# MODULOS.net
KiCad netlist of a schematic drawn in Altium Designer
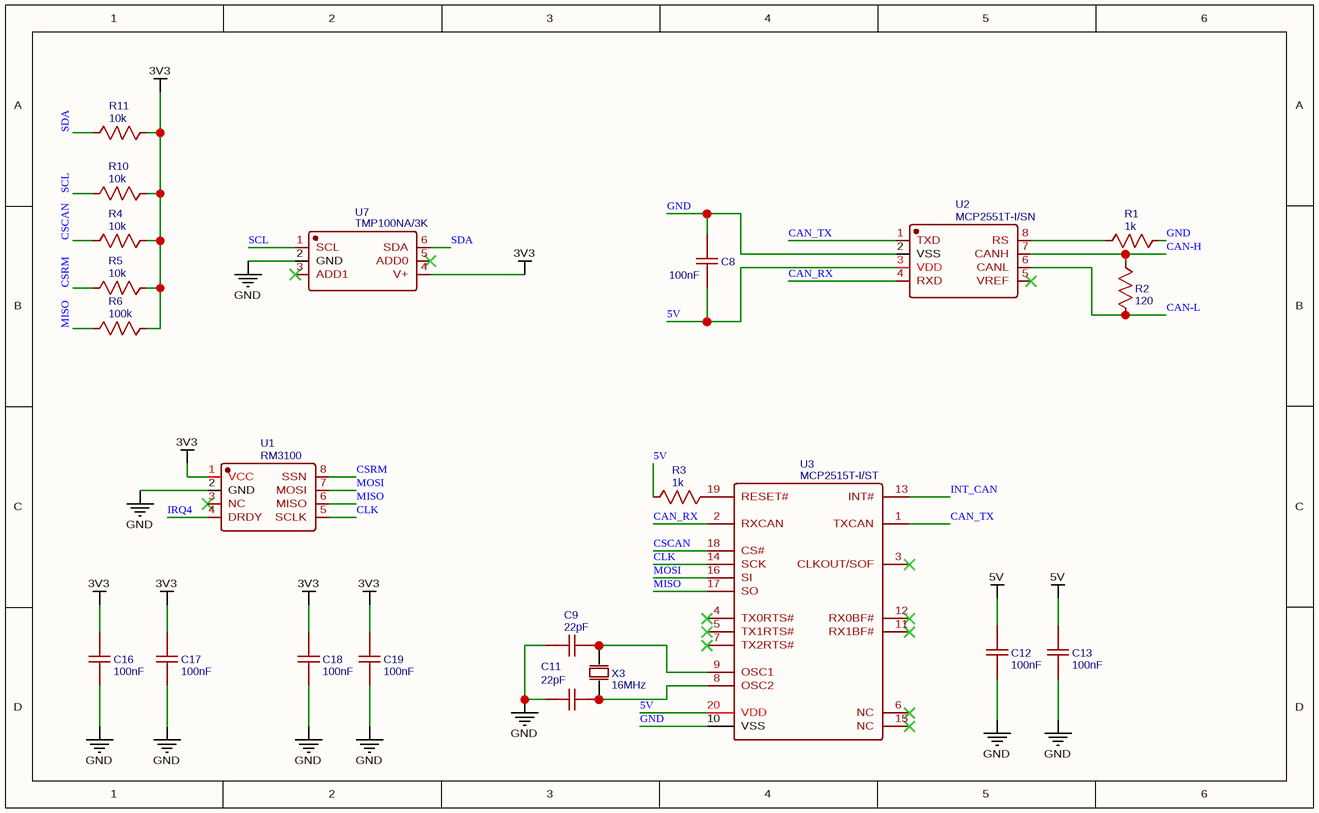
[diagram p0: MODULOS.schdoc]

(export (version "E")
  (design (tool "Eeschema 10.0.6"))
  (components
    (comp (ref "C8")
      (value "100nF")
      (fields
        (field (name "BOM_SUPPLIER PART") "C49678")
        (field (name "BOM_MANUFACTURER PART") "CC0805KRX7R9BB104")
        (field (name "CONTRIBUTOR") "LCEDA_Lib")
      )
      (libsource (lib "altium-import") (part "root_3_100nF_"))
    )
    (comp (ref "C9")
      (value "22pF")
      (fields
        (field (name "BOM_SUPPLIER PART") "C105623")
        (field (name "BOM_MANUFACTURER PART") "CC0805JRNPO9BN220")
        (field (name "CONTRIBUTOR") "LCEDA_Lib")
      )
      (libsource (lib "altium-import") (part "root_0_22pF_"))
    )
    (comp (ref "C11")
      (value "22pF")
      (fields
        (field (name "BOM_SUPPLIER PART") "C105623")
        (field (name "BOM_MANUFACTURER PART") "CC0805JRNPO9BN220")
        (field (name "CONTRIBUTOR") "LCEDA_Lib")
      )
      (libsource (lib "altium-import") (part "root_2_22pF_"))
    )
    (comp (ref "C12")
      (value "100nF")
      (fields
        (field (name "BOM_SUPPLIER PART") "C49678")
        (field (name "BOM_MANUFACTURER PART") "CC0805KRX7R9BB104")
        (field (name "CONTRIBUTOR") "LCEDA_Lib")
      )
      (libsource (lib "altium-import") (part "root_1_100nF_"))
    )
    (comp (ref "C13")
      (value "100nF")
      (fields
        (field (name "BOM_SUPPLIER PART") "C49678")
        (field (name "BOM_MANUFACTURER PART") "CC0805KRX7R9BB104")
        (field (name "CONTRIBUTOR") "LCEDA_Lib")
      )
      (libsource (lib "altium-import") (part "root_1_100nF_"))
    )
    (comp (ref "C16")
      (value "100nF")
      (fields
        (field (name "BOM_SUPPLIER PART") "C49678")
        (field (name "BOM_MANUFACTURER PART") "CC0805KRX7R9BB104")
        (field (name "CONTRIBUTOR") "LCEDA_Lib")
      )
      (libsource (lib "altium-import") (part "root_1_100nF_"))
    )
    (comp (ref "C17")
      (value "100nF")
      (fields
        (field (name "BOM_SUPPLIER PART") "C49678")
        (field (name "BOM_MANUFACTURER PART") "CC0805KRX7R9BB104")
        (field (name "CONTRIBUTOR") "LCEDA_Lib")
      )
      (libsource (lib "altium-import") (part "root_1_100nF_"))
    )
    (comp (ref "C18")
      (value "100nF")
      (fields
        (field (name "BOM_SUPPLIER PART") "C49678")
        (field (name "BOM_MANUFACTURER PART") "CC0805KRX7R9BB104")
        (field (name "CONTRIBUTOR") "LCEDA_Lib")
      )
      (libsource (lib "altium-import") (part "root_1_100nF_"))
    )
    (comp (ref "C19")
      (value "100nF")
      (fields
        (field (name "BOM_SUPPLIER PART") "C49678")
        (field (name "BOM_MANUFACTURER PART") "CC0805KRX7R9BB104")
        (field (name "CONTRIBUTOR") "LCEDA_Lib")
      )
      (libsource (lib "altium-import") (part "root_1_100nF_"))
    )
    (comp (ref "R1")
      (value "1k")
      (fields
        (field (name "BOM_SUPPLIER PART") "C17513")
        (field (name "BOM_MANUFACTURER PART") "0805W8F1001T5E")
        (field (name "CONTRIBUTOR") "LCEDA_Lib")
      )
      (libsource (lib "altium-import") (part "root_0_1k_"))
    )
    (comp (ref "R2")
      (value "120")
      (fields
        (field (name "BOM_SUPPLIER PART") "C269726")
        (field (name "BOM_MANUFACTURER PART") "RMC 0805 120R J N")
        (field (name "CONTRIBUTOR") "LCEDA_Lib")
      )
      (libsource (lib "altium-import") (part "root_1_120_"))
    )
    (comp (ref "R3")
      (value "1k")
      (fields
        (field (name "BOM_SUPPLIER PART") "C17513")
        (field (name "BOM_MANUFACTURER PART") "0805W8F1001T5E")
        (field (name "CONTRIBUTOR") "LCEDA_Lib")
      )
      (libsource (lib "altium-import") (part "root_0_1k_"))
    )
    (comp (ref "R4")
      (value "10k")
      (fields
        (field (name "BOM_SUPPLIER PART") "C169253")
        (field (name "BOM_MANUFACTURER PART") "ERJ6ENF1002V")
        (field (name "CONTRIBUTOR") "LCEDA_Lib")
      )
      (libsource (lib "altium-import") (part "root_2_10k_"))
    )
    (comp (ref "R5")
      (value "10k")
      (fields
        (field (name "BOM_SUPPLIER PART") "C169253")
        (field (name "BOM_MANUFACTURER PART") "ERJ6ENF1002V")
        (field (name "CONTRIBUTOR") "LCEDA_Lib")
      )
      (libsource (lib "altium-import") (part "root_2_10k_"))
    )
    (comp (ref "R6")
      (value "100k")
      (fields
        (field (name "BOM_SUPPLIER PART") "C429267")
        (field (name "BOM_MANUFACTURER PART") "CR0805F340RP05")
        (field (name "CONTRIBUTOR") "LCEDA_Lib")
      )
      (libsource (lib "altium-import") (part "root_2_100k_"))
    )
    (comp (ref "R10")
      (value "10k")
      (fields
        (field (name "BOM_SUPPLIER PART") "C169253")
        (field (name "BOM_MANUFACTURER PART") "ERJ6ENF1002V")
        (field (name "CONTRIBUTOR") "LCEDA_Lib")
      )
      (libsource (lib "altium-import") (part "root_2_10k_"))
    )
    (comp (ref "R11")
      (value "10k")
      (fields
        (field (name "BOM_SUPPLIER PART") "C169253")
        (field (name "BOM_MANUFACTURER PART") "ERJ6ENF1002V")
        (field (name "CONTRIBUTOR") "LCEDA_Lib")
      )
      (libsource (lib "altium-import") (part "root_2_10k_"))
    )
    (comp (ref "U1")
      (value "RM3100")
      (fields (field (name "CONTRIBUTOR") "nitnerolf1"))
      (libsource (lib "altium-import") (part "root_0_RM3100_"))
    )
    (comp (ref "U2")
      (value "MCP2551T-I/SN")
      (fields (field (name "BOM_SUPPLIER PART") "C49558"))
      (libsource (lib "altium-import") (part "root_0_MCP2551T-I/SN_"))
    )
    (comp (ref "U3")
      (value "MCP2515T-I/ST")
      (fields (field (name "BOM_SUPPLIER PART") "C185941") (field (name "CONTRIBUTOR") "LCSC"))
      (libsource (lib "altium-import") (part "root_0_MCP2515T-I/ST_"))
    )
    (comp (ref "U7")
      (value "TMP100NA/3K")
      (fields (field (name "BOM_SUPPLIER PART") "C31810"))
      (libsource (lib "altium-import") (part "root_0_TMP100NA/3K_"))
    )
    (comp (ref "X3")
      (value "16MHz")
      (fields
        (field (name "BOM_MANUFACTURER PART") "X49SD16MSD2SC")
        (field (name "BOM_SUPPLIER PART") "C16212")
      )
      (libsource (lib "altium-import") (part "root_1_16MHz_"))
    )
  )
  (nets
    (net (code "1") (name "/CAN-H") (class "Default")
      (node (ref "R2") (pin "2") (pinfunction "2_2") (pintype "passive"))
      (node (ref "U2") (pin "7") (pinfunction "CANH_7") (pintype "passive"))
    )
    (net (code "2") (name "/CAN-L") (class "Default")
      (node (ref "R2") (pin "1") (pinfunction "1_1") (pintype "passive"))
      (node (ref "U2") (pin "6") (pinfunction "CANL_6") (pintype "passive"))
    )
    (net (code "3") (name "/CAN_RX") (class "Default")
      (node (ref "U2") (pin "4") (pinfunction "RXD_4") (pintype "passive"))
      (node (ref "U3") (pin "2") (pinfunction "RXCAN_2") (pintype "passive"))
    )
    (net (code "4") (name "/CAN_TX") (class "Default")
      (node (ref "U2") (pin "1") (pinfunction "TXD_1") (pintype "passive"))
      (node (ref "U3") (pin "1") (pinfunction "TXCAN_1") (pintype "passive"))
    )
    (net (code "5") (name "/CLK") (class "Default")
      (node (ref "U1") (pin "5") (pinfunction "SCLK_5") (pintype "passive"))
      (node (ref "U3") (pin "14") (pinfunction "SCK_14") (pintype "passive"))
    )
    (net (code "6") (name "/CSCAN") (class "Default")
      (node (ref "R4") (pin "2") (pinfunction "2_2") (pintype "passive"))
      (node (ref "U3") (pin "18") (pinfunction "CS#_18") (pintype "passive"))
    )
    (net (code "7") (name "/CSRM") (class "Default")
      (node (ref "R5") (pin "2") (pinfunction "2_2") (pintype "passive"))
      (node (ref "U1") (pin "8") (pinfunction "SSN_8") (pintype "passive"))
    )
    (net (code "8") (name "/INT_CAN") (class "Default")
      (node (ref "U3") (pin "13") (pinfunction "INT#_13") (pintype "passive"))
    )
    (net (code "9") (name "/IRQ4") (class "Default")
      (node (ref "U1") (pin "4") (pinfunction "DRDY_4") (pintype "passive"))
    )
    (net (code "10") (name "/MISO") (class "Default")
      (node (ref "R6") (pin "2") (pinfunction "2_2") (pintype "passive"))
      (node (ref "U1") (pin "6") (pinfunction "MISO_6") (pintype "passive"))
      (node (ref "U3") (pin "17") (pinfunction "SO_17") (pintype "passive"))
    )
    (net (code "11") (name "/MOSI") (class "Default")
      (node (ref "U1") (pin "7") (pinfunction "MOSI_7") (pintype "passive"))
      (node (ref "U3") (pin "16") (pinfunction "SI_16") (pintype "passive"))
    )
    (net (code "12") (name "/SCL") (class "Default")
      (node (ref "R10") (pin "2") (pinfunction "2_2") (pintype "passive"))
      (node (ref "U7") (pin "1") (pinfunction "SCL_1") (pintype "passive"))
    )
    (net (code "13") (name "/SDA") (class "Default")
      (node (ref "R11") (pin "2") (pinfunction "2_2") (pintype "passive"))
      (node (ref "U7") (pin "6") (pinfunction "SDA_6") (pintype "passive"))
    )
    (net (code "14") (name "3V3") (class "Default")
      (node (ref "C16") (pin "2") (pinfunction "2_2") (pintype "passive"))
      (node (ref "C17") (pin "2") (pinfunction "2_2") (pintype "passive"))
      (node (ref "C18") (pin "2") (pinfunction "2_2") (pintype "passive"))
      (node (ref "C19") (pin "2") (pinfunction "2_2") (pintype "passive"))
      (node (ref "R10") (pin "1") (pinfunction "1_1") (pintype "passive"))
      (node (ref "R11") (pin "1") (pinfunction "1_1") (pintype "passive"))
      (node (ref "R4") (pin "1") (pinfunction "1_1") (pintype "passive"))
      (node (ref "R5") (pin "1") (pinfunction "1_1") (pintype "passive"))
      (node (ref "R6") (pin "1") (pinfunction "1_1") (pintype "passive"))
      (node (ref "U1") (pin "1") (pinfunction "VCC_1") (pintype "passive"))
      (node (ref "U7") (pin "4") (pinfunction "V+_4") (pintype "passive"))
    )
    (net (code "15") (name "5V") (class "Default")
      (node (ref "C12") (pin "2") (pinfunction "2_2") (pintype "passive"))
      (node (ref "C13") (pin "2") (pinfunction "2_2") (pintype "passive"))
      (node (ref "C8") (pin "2") (pinfunction "2_2") (pintype "passive"))
      (node (ref "R3") (pin "1") (pinfunction "1_1") (pintype "passive"))
      (node (ref "U2") (pin "3") (pinfunction "VDD_3") (pintype "passive"))
      (node (ref "U3") (pin "20") (pinfunction "VDD_20") (pintype "passive"))
    )
    (net (code "16") (name "GND") (class "Default")
      (node (ref "C11") (pin "2") (pinfunction "2_2") (pintype "passive"))
      (node (ref "C12") (pin "1") (pinfunction "1_1") (pintype "passive"))
      (node (ref "C13") (pin "1") (pinfunction "1_1") (pintype "passive"))
      (node (ref "C16") (pin "1") (pinfunction "1_1") (pintype "passive"))
      (node (ref "C17") (pin "1") (pinfunction "1_1") (pintype "passive"))
      (node (ref "C18") (pin "1") (pinfunction "1_1") (pintype "passive"))
      (node (ref "C19") (pin "1") (pinfunction "1_1") (pintype "passive"))
      (node (ref "C8") (pin "1") (pinfunction "1_1") (pintype "passive"))
      (node (ref "C9") (pin "1") (pinfunction "1_1") (pintype "passive"))
      (node (ref "R1") (pin "2") (pinfunction "2_2") (pintype "passive"))
      (node (ref "U1") (pin "2") (pinfunction "GND_2") (pintype "passive"))
      (node (ref "U2") (pin "2") (pinfunction "VSS_2") (pintype "passive"))
      (node (ref "U3") (pin "10") (pinfunction "VSS_10") (pintype "passive"))
      (node (ref "U7") (pin "2") (pinfunction "GND_2") (pintype "passive"))
    )
    (net (code "17") (name "Net-(U2-RS)") (class "Default")
      (node (ref "R1") (pin "1") (pinfunction "1_1") (pintype "passive"))
      (node (ref "U2") (pin "8") (pinfunction "RS_8") (pintype "passive"))
    )
    (net (code "18") (name "Net-(U3-OSC1)") (class "Default")
      (node (ref "C9") (pin "2") (pinfunction "2_2") (pintype "passive"))
      (node (ref "U3") (pin "9") (pinfunction "OSC1_9") (pintype "passive"))
      (node (ref "X3") (pin "1") (pinfunction "OSC1_1") (pintype "passive"))
    )
    (net (code "19") (name "Net-(U3-OSC2)") (class "Default")
      (node (ref "C11") (pin "1") (pinfunction "1_1") (pintype "passive"))
      (node (ref "U3") (pin "8") (pinfunction "OSC2_8") (pintype "passive"))
      (node (ref "X3") (pin "2") (pinfunction "OSC2_2") (pintype "passive"))
    )
    (net (code "20") (name "Net-(U3-RESET#)") (class "Default")
      (node (ref "R3") (pin "2") (pinfunction "2_2") (pintype "passive"))
      (node (ref "U3") (pin "19") (pinfunction "RESET#_19") (pintype "passive"))
    )
    (net (code "21") (name "unconnected-(U1-NC-Pad3)") (class "Default")
      (node (ref "U1") (pin "3") (pinfunction "NC_3") (pintype "passive+no_connect"))
    )
    (net (code "22") (name "unconnected-(U2-VREF-Pad5)") (class "Default")
      (node (ref "U2") (pin "5") (pinfunction "VREF_5") (pintype "passive+no_connect"))
    )
    (net (code "23") (name "unconnected-(U3-CLKOUT{slash}SOF-Pad3)") (class "Default")
      (node (ref "U3") (pin "3") (pinfunction "CLKOUT/SOF_3") (pintype "passive+no_connect"))
    )
    (net (code "24") (name "unconnected-(U3-NC-Pad6)") (class "Default")
      (node (ref "U3") (pin "6") (pinfunction "NC_6") (pintype "passive+no_connect"))
    )
    (net (code "25") (name "unconnected-(U3-NC-Pad15)") (class "Default")
      (node (ref "U3") (pin "15") (pinfunction "NC_15") (pintype "passive+no_connect"))
    )
    (net (code "26") (name "unconnected-(U3-RX0BF#-Pad12)") (class "Default")
      (node (ref "U3") (pin "12") (pinfunction "RX0BF#_12") (pintype "passive+no_connect"))
    )
    (net (code "27") (name "unconnected-(U3-RX1BF#-Pad11)") (class "Default")
      (node (ref "U3") (pin "11") (pinfunction "RX1BF#_11") (pintype "passive+no_connect"))
    )
    (net (code "28") (name "unconnected-(U3-TX0RTS#-Pad4)") (class "Default")
      (node (ref "U3") (pin "4") (pinfunction "TX0RTS#_4") (pintype "passive+no_connect"))
    )
    (net (code "29") (name "unconnected-(U3-TX1RTS#-Pad5)") (class "Default")
      (node (ref "U3") (pin "5") (pinfunction "TX1RTS#_5") (pintype "passive+no_connect"))
    )
    (net (code "30") (name "unconnected-(U3-TX2RTS#-Pad7)") (class "Default")
      (node (ref "U3") (pin "7") (pinfunction "TX2RTS#_7") (pintype "passive+no_connect"))
    )
    (net (code "31") (name "unconnected-(U7-ADD0-Pad5)") (class "Default")
      (node (ref "U7") (pin "5") (pinfunction "ADD0_5") (pintype "passive+no_connect"))
    )
    (net (code "32") (name "unconnected-(U7-ADD1-Pad3)") (class "Default")
      (node (ref "U7") (pin "3") (pinfunction "ADD1_3") (pintype "passive+no_connect"))
    )
  )
)
